# LED_Board_control.net
KiCad netlist of a schematic drawn in Altium Designer
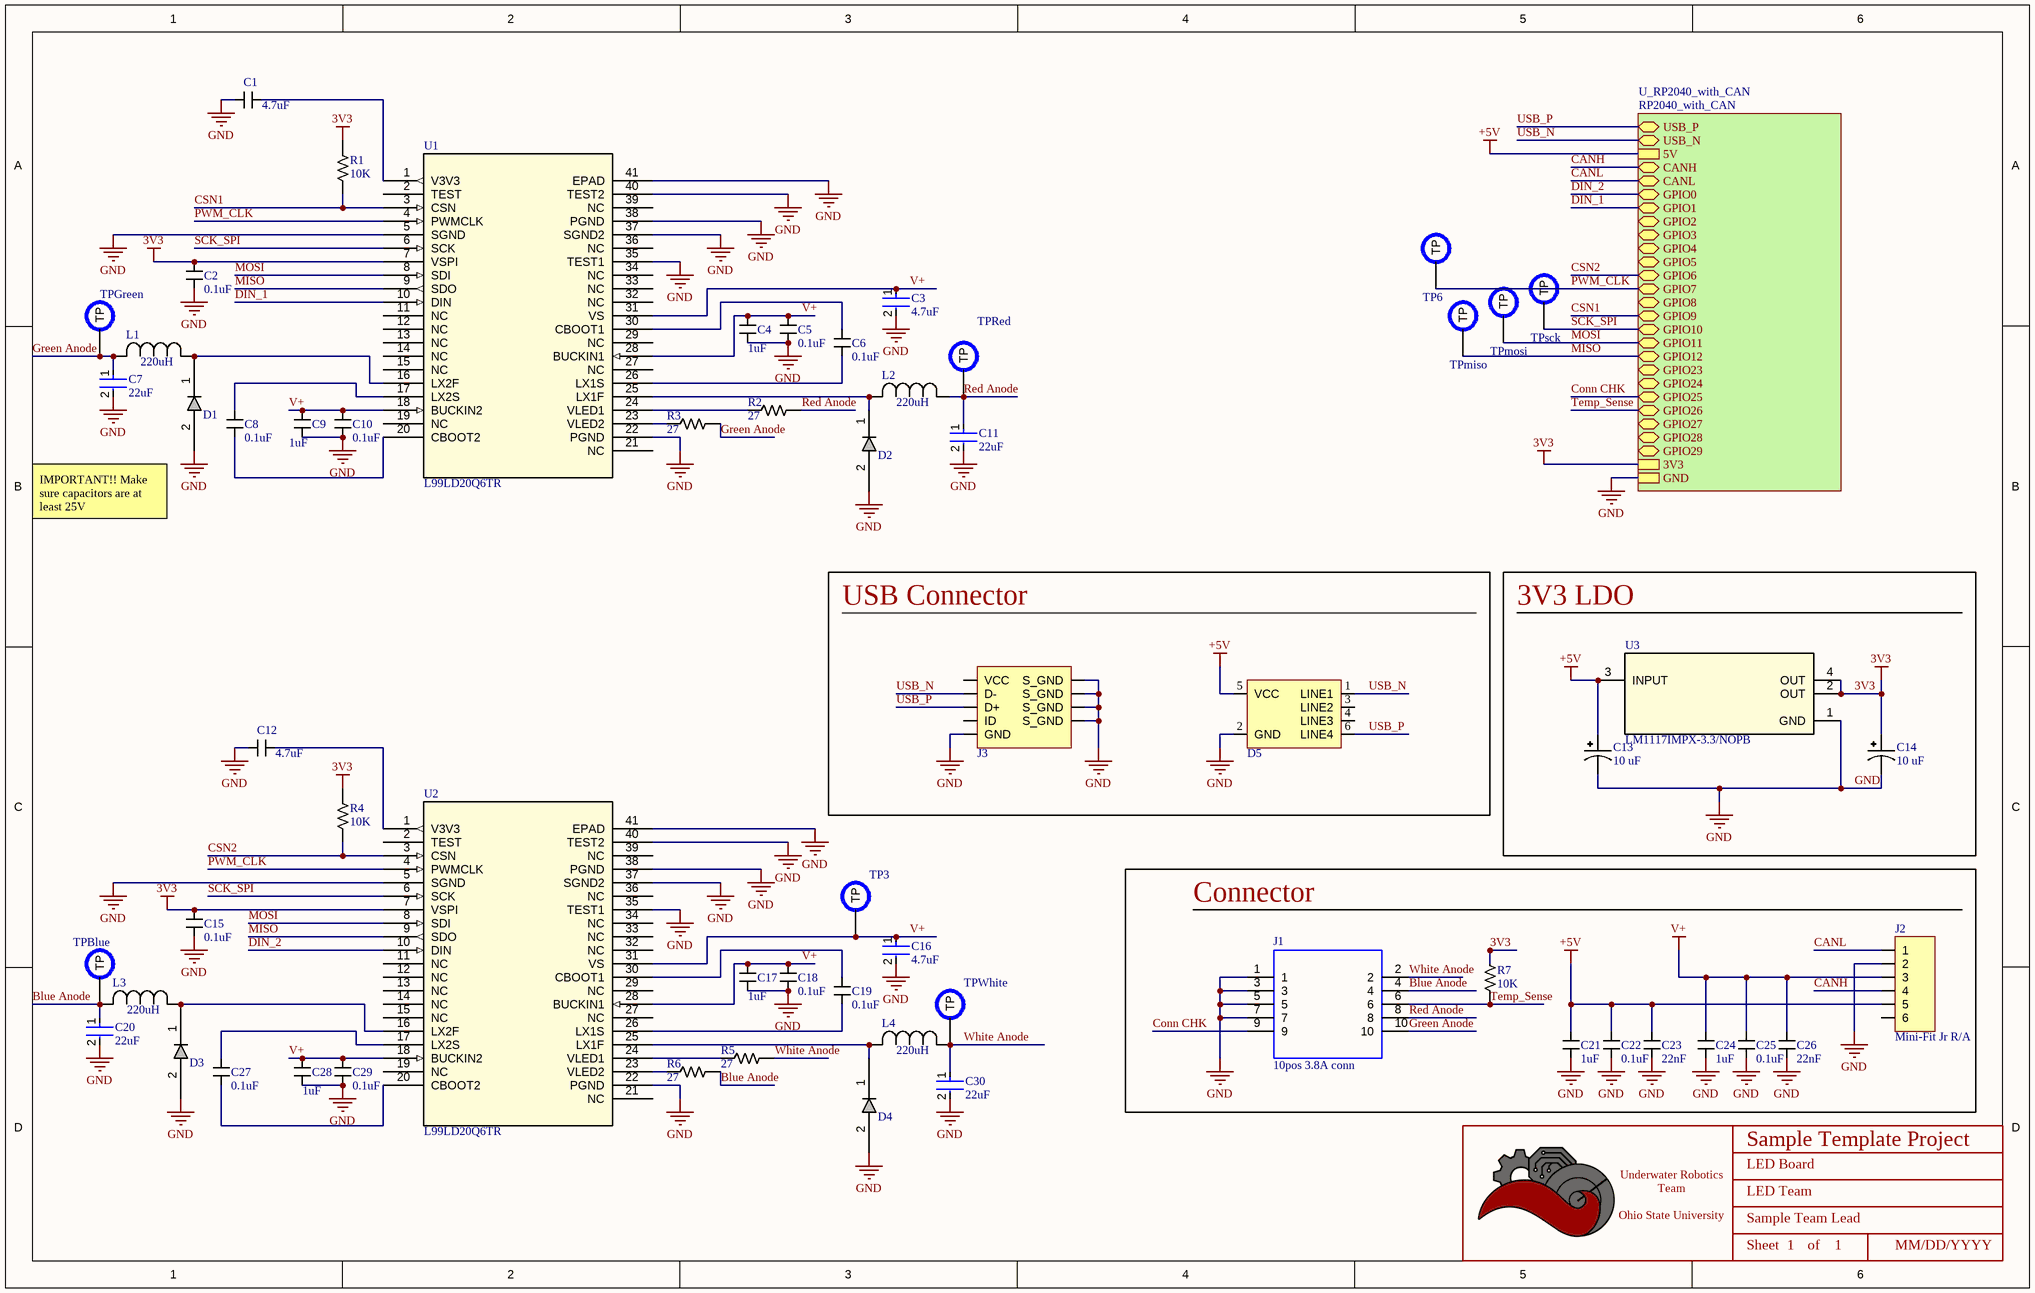
[diagram p0: LED_Board_control.SchDoc]

(export (version "E")
  (design (tool "Eeschema 10.0.6"))
  (components
    (comp (ref "*")
      (value "Title_Block")
      (footprint "LOGO")
      (description "UWRT Schematic Title Block Template\r\n\r\nCreated June 2021, Dylan Trainor")
      (libsource (lib "UWRT") (part "Title_Block"))
    )
    (comp (ref "C1")
      (value "4.7uF")
      (footprint "CAPACITOR_0603")
      (description "Cap 4.7uF 6.3V +/-10%\r\nCeramic 0603")
      (fields
        (field (name "TOLERANCE") "+/- 10%")
        (field (name "VOLTAGE") "6.3V")
        (field (name "MADE BY") "Robert Pafford")
      )
      (libsource (lib "Capacitors") (part "CAPACITOR_4.7uF_0603"))
    )
    (comp (ref "C2")
      (value "0.1uF")
      (footprint "CAPACITOR_0603")
      (description "Cap 100nF 6.3V +/-10%\r\nCeramic 0603")
      (fields
        (field (name "TOLERANCE") "+/- 10%")
        (field (name "VOLTAGE") "6.3V")
        (field (name "MADE BY") "Flip B")
      )
      (libsource (lib "Capacitors") (part "CAPACITOR_0.1uF_0603_1"))
    )
    (comp (ref "C3")
      (value "4.7uF")
      (footprint "CAPACITOR_0603")
      (description "Chip Multilayer Ceramic Capacitors for General Purpose, 0603, 4.7uF, X5R, 15%, 20%, 35V")
      (fields (field (name "TOLERANCE") "20%"))
      (libsource (lib "Capacitors") (part "CAP CERM 4.7UF 20% 35V"))
    )
    (comp (ref "C4")
      (value "1uF")
      (footprint "CAPACITOR_0603")
      (description "Cap 1uF 25V +/-10%\r\nCeramic 0603")
      (fields
        (field (name "TOLERANCE") "+/- 10%")
        (field (name "VOLTAGE") "16V")
        (field (name "MADE BY") "Flip B")
      )
      (libsource (lib "Capacitors") (part "CAPACITOR_1uF_0603_25V"))
    )
    (comp (ref "C5")
      (value "0.1uF")
      (footprint "CAPACITOR_0603")
      (description "Cap 100nF 25V +/-10%\r\nCeramic 0603")
      (fields
        (field (name "TOLERANCE") "+/- 10%")
        (field (name "VOLTAGE") "6.3V")
        (field (name "MADE BY") "Flip B")
      )
      (libsource (lib "Capacitors") (part "CAPACITOR_0.1uF_0603_25V"))
    )
    (comp (ref "C6")
      (value "0.1uF")
      (footprint "CAPACITOR_0603")
      (description "Cap 100nF 25V +/-10%\r\nCeramic 0603")
      (fields
        (field (name "TOLERANCE") "+/- 10%")
        (field (name "VOLTAGE") "6.3V")
        (field (name "MADE BY") "Flip B")
      )
      (libsource (lib "Capacitors") (part "CAPACITOR_0.1uF_0603_25V"))
    )
    (comp (ref "C7")
      (value "22uF")
      (footprint "FP-C2012-125-0_2-MFG")
      (description "Multilayer Ceramic Capacitors 22μF ±20% 35V X5R SMD 0805")
      (fields (field (name "TOLERANCE") "20%"))
      (libsource (lib "Altium Content Vault") (part "b4654b650e69147ec39a6b967a45e02"))
    )
    (comp (ref "C8")
      (value "0.1uF")
      (footprint "CAPACITOR_0603")
      (description "Cap 100nF 25V +/-10%\r\nCeramic 0603")
      (fields
        (field (name "TOLERANCE") "+/- 10%")
        (field (name "VOLTAGE") "6.3V")
        (field (name "MADE BY") "Flip B")
      )
      (libsource (lib "Capacitors") (part "CAPACITOR_0.1uF_0603_25V"))
    )
    (comp (ref "C9")
      (value "1uF")
      (footprint "CAPACITOR_0603")
      (description "Cap 1uF 25V +/-10%\r\nCeramic 0603")
      (fields
        (field (name "TOLERANCE") "+/- 10%")
        (field (name "VOLTAGE") "16V")
        (field (name "MADE BY") "Flip B")
      )
      (libsource (lib "Capacitors") (part "CAPACITOR_1uF_0603_25V"))
    )
    (comp (ref "C10")
      (value "0.1uF")
      (footprint "CAPACITOR_0603")
      (description "Cap 100nF 25V +/-10%\r\nCeramic 0603")
      (fields
        (field (name "TOLERANCE") "+/- 10%")
        (field (name "VOLTAGE") "6.3V")
        (field (name "MADE BY") "Flip B")
      )
      (libsource (lib "Capacitors") (part "CAPACITOR_0.1uF_0603_25V"))
    )
    (comp (ref "C11")
      (value "22uF")
      (footprint "FP-C2012-125-0_2-MFG")
      (description "Multilayer Ceramic Capacitors 22μF ±20% 35V X5R SMD 0805")
      (fields (field (name "TOLERANCE") "20%"))
      (libsource (lib "Altium Content Vault") (part "b4654b650e69147ec39a6b967a45e02"))
    )
    (comp (ref "C12")
      (value "4.7uF")
      (footprint "CAPACITOR_0603")
      (description "Cap 4.7uF 6.3V +/-10%\r\nCeramic 0603")
      (fields
        (field (name "TOLERANCE") "+/- 10%")
        (field (name "VOLTAGE") "6.3V")
        (field (name "MADE BY") "Robert Pafford")
      )
      (libsource (lib "Capacitors") (part "CAPACITOR_4.7uF_0603"))
    )
    (comp (ref "C13")
      (value "10uF Tantalum 16V")
      (footprint "CAPACITOR_1206 - POLAR")
      (description "Cap 10uF 16V +/-20%\r\nTantalum 1206")
      (fields
        (field (name "TOLERANCE") "+/- 10%")
        (field (name "VOLTAGE") "16V")
        (field (name "VALUE (UF)") "10 uF")
        (field (name "MADE BY") "Dylan T")
      )
      (libsource (lib "Capacitors") (part "CAPACITOR_10uF_1206_Tantalum_1"))
    )
    (comp (ref "C14")
      (value "10uF Tantalum 16V")
      (footprint "CAPACITOR_1206 - POLAR")
      (description "Cap 10uF 16V +/-20%\r\nTantalum 1206")
      (fields
        (field (name "TOLERANCE") "+/- 10%")
        (field (name "VOLTAGE") "16V")
        (field (name "VALUE (UF)") "10 uF")
        (field (name "MADE BY") "Dylan T")
      )
      (libsource (lib "Capacitors") (part "CAPACITOR_10uF_1206_Tantalum_1"))
    )
    (comp (ref "C15")
      (value "0.1uF")
      (footprint "CAPACITOR_0603")
      (description "Cap 100nF 6.3V +/-10%\r\nCeramic 0603")
      (fields
        (field (name "TOLERANCE") "+/- 10%")
        (field (name "VOLTAGE") "6.3V")
        (field (name "MADE BY") "Flip B")
      )
      (libsource (lib "Capacitors") (part "CAPACITOR_0.1uF_0603_1"))
    )
    (comp (ref "C16")
      (value "4.7uF")
      (footprint "CAPACITOR_0603")
      (description "Chip Multilayer Ceramic Capacitors for General Purpose, 0603, 4.7uF, X5R, 15%, 20%, 35V")
      (fields (field (name "TOLERANCE") "20%"))
      (libsource (lib "Capacitors") (part "CAP CERM 4.7UF 20% 35V"))
    )
    (comp (ref "C17")
      (value "1uF")
      (footprint "CAPACITOR_0603")
      (description "Cap 1uF 25V +/-10%\r\nCeramic 0603")
      (fields
        (field (name "TOLERANCE") "+/- 10%")
        (field (name "VOLTAGE") "16V")
        (field (name "MADE BY") "Flip B")
      )
      (libsource (lib "Capacitors") (part "CAPACITOR_1uF_0603_25V"))
    )
    (comp (ref "C18")
      (value "0.1uF")
      (footprint "CAPACITOR_0603")
      (description "Cap 100nF 25V +/-10%\r\nCeramic 0603")
      (fields
        (field (name "TOLERANCE") "+/- 10%")
        (field (name "VOLTAGE") "6.3V")
        (field (name "MADE BY") "Flip B")
      )
      (libsource (lib "Capacitors") (part "CAPACITOR_0.1uF_0603_25V"))
    )
    (comp (ref "C19")
      (value "0.1uF")
      (footprint "CAPACITOR_0603")
      (description "Cap 100nF 25V +/-10%\r\nCeramic 0603")
      (fields
        (field (name "TOLERANCE") "+/- 10%")
        (field (name "VOLTAGE") "6.3V")
        (field (name "MADE BY") "Flip B")
      )
      (libsource (lib "Capacitors") (part "CAPACITOR_0.1uF_0603_25V"))
    )
    (comp (ref "C20")
      (value "22uF")
      (footprint "FP-C2012-125-0_2-MFG")
      (description "Multilayer Ceramic Capacitors 22μF ±20% 35V X5R SMD 0805")
      (fields (field (name "TOLERANCE") "20%"))
      (libsource (lib "Altium Content Vault") (part "b4654b650e69147ec39a6b967a45e02"))
    )
    (comp (ref "C21")
      (value "1uF")
      (footprint "CAPACITOR_0603")
      (description "Cap 1uF 16V +/-10%\r\nCeramic 0603")
      (fields
        (field (name "TOLERANCE") "+/- 10%")
        (field (name "VOLTAGE") "16V")
        (field (name "MADE BY") "Flip B")
      )
      (libsource (lib "Capacitors") (part "CAPACITOR_1uF_0603"))
    )
    (comp (ref "C22")
      (value "0.1uF")
      (footprint "CAPACITOR_0805")
      (description "Cap 100nF 50V +/-10%\r\nCeramic 0805")
      (fields
        (field (name "TOLERANCE") "+/- 10%")
        (field (name "VOLTAGE") "50V")
        (field (name "MADE BY") "Robert Pafford")
      )
      (libsource (lib "Capacitors") (part "CAPACITOR_0.1uF_0805"))
    )
    (comp (ref "C23")
      (value "22nF")
      (footprint "CAPACITOR_0402")
      (description "Cap 22nF 25V +/-10%\r\nCeramic 0402")
      (fields
        (field (name "TOLERANCE") "+/- 10%")
        (field (name "VOLTAGE") "25V")
        (field (name "MADE BY") "Robert Pafford")
      )
      (libsource (lib "Capacitors") (part "CAPACITOR_0.022uF_0402"))
    )
    (comp (ref "C24")
      (value "1uF")
      (footprint "CAPACITOR_0603")
      (description "Cap 1uF 16V +/-10%\r\nCeramic 0603")
      (fields
        (field (name "TOLERANCE") "+/- 10%")
        (field (name "VOLTAGE") "16V")
        (field (name "MADE BY") "Flip B")
      )
      (libsource (lib "Capacitors") (part "CAPACITOR_1uF_0603"))
    )
    (comp (ref "C25")
      (value "0.1uF")
      (footprint "CAPACITOR_0805")
      (description "Cap 100nF 50V +/-10%\r\nCeramic 0805")
      (fields
        (field (name "TOLERANCE") "+/- 10%")
        (field (name "VOLTAGE") "50V")
        (field (name "MADE BY") "Robert Pafford")
      )
      (libsource (lib "Capacitors") (part "CAPACITOR_0.1uF_0805"))
    )
    (comp (ref "C26")
      (value "22nF")
      (footprint "CAPACITOR_0402")
      (description "Cap 22nF 25V +/-10%\r\nCeramic 0402")
      (fields
        (field (name "TOLERANCE") "+/- 10%")
        (field (name "VOLTAGE") "25V")
        (field (name "MADE BY") "Robert Pafford")
      )
      (libsource (lib "Capacitors") (part "CAPACITOR_0.022uF_0402"))
    )
    (comp (ref "C27")
      (value "0.1uF")
      (footprint "CAPACITOR_0603")
      (description "Cap 100nF 25V +/-10%\r\nCeramic 0603")
      (fields
        (field (name "TOLERANCE") "+/- 10%")
        (field (name "VOLTAGE") "6.3V")
        (field (name "MADE BY") "Flip B")
      )
      (libsource (lib "Capacitors") (part "CAPACITOR_0.1uF_0603_25V"))
    )
    (comp (ref "C28")
      (value "1uF")
      (footprint "CAPACITOR_0603")
      (description "Cap 1uF 25V +/-10%\r\nCeramic 0603")
      (fields
        (field (name "TOLERANCE") "+/- 10%")
        (field (name "VOLTAGE") "16V")
        (field (name "MADE BY") "Flip B")
      )
      (libsource (lib "Capacitors") (part "CAPACITOR_1uF_0603_25V"))
    )
    (comp (ref "C29")
      (value "0.1uF")
      (footprint "CAPACITOR_0603")
      (description "Cap 100nF 25V +/-10%\r\nCeramic 0603")
      (fields
        (field (name "TOLERANCE") "+/- 10%")
        (field (name "VOLTAGE") "6.3V")
        (field (name "MADE BY") "Flip B")
      )
      (libsource (lib "Capacitors") (part "CAPACITOR_0.1uF_0603_25V"))
    )
    (comp (ref "C30")
      (value "22uF")
      (footprint "FP-C2012-125-0_2-MFG")
      (description "Multilayer Ceramic Capacitors 22μF ±20% 35V X5R SMD 0805")
      (fields (field (name "TOLERANCE") "20%"))
      (libsource (lib "Altium Content Vault") (part "b4654b650e69147ec39a6b967a45e02"))
    )
    (comp (ref "D1")
      (value "CCS15S40,L3F")
      (footprint "SOD-963   CST2C_TOS")
      (description "DIODE SCHOTTKY 40V 1.5A CST2C")
      (fields (field (name "COPYRIGHT") "Copyright (C) 2023 Ultra Librarian. All rights reserved."))
      (libsource (lib "Diodes") (part "SCHOTTKY_40V_1.5A"))
    )
    (comp (ref "D2")
      (value "CCS15S40,L3F")
      (footprint "SOD-963   CST2C_TOS")
      (description "DIODE SCHOTTKY 40V 1.5A CST2C")
      (fields (field (name "COPYRIGHT") "Copyright (C) 2023 Ultra Librarian. All rights reserved."))
      (libsource (lib "Diodes") (part "SCHOTTKY_40V_1.5A"))
    )
    (comp (ref "D3")
      (value "CCS15S40,L3F")
      (footprint "SOD-963   CST2C_TOS")
      (description "DIODE SCHOTTKY 40V 1.5A CST2C")
      (fields (field (name "COPYRIGHT") "Copyright (C) 2023 Ultra Librarian. All rights reserved."))
      (libsource (lib "Diodes") (part "SCHOTTKY_40V_1.5A"))
    )
    (comp (ref "D4")
      (value "CCS15S40,L3F")
      (footprint "SOD-963   CST2C_TOS")
      (description "DIODE SCHOTTKY 40V 1.5A CST2C")
      (fields (field (name "COPYRIGHT") "Copyright (C) 2023 Ultra Librarian. All rights reserved."))
      (libsource (lib "Diodes") (part "SCHOTTKY_40V_1.5A"))
    )
    (comp (ref "D5")
      (value "TVS DIODE 5VWM 25VC SOT23-6")
      (footprint "SOT 23-6L")
      (description "25V Clamp 6A (8/20µs) Ipp Tvs Diode Surface Mount SOT-23-6")
      (fields (field (name "MADE BY") "Robert Pafford"))
      (libsource (lib "Diodes") (part "RCLAMP0504S.TCT"))
    )
    (comp (ref "J1")
      (value "10pos 3.8A conn")
      (footprint "Connectors:SAMTEC-LS2-105-01-X-D-RA1")
      (description "10 Position Connector Self Mating, Non-Gendered, Hermaphroditic Through Hole, Right Angle Gold")
      (fields (field (name "MP") "SAMTEC-LS2-105-01-X-D-RA1"))
      (libsource (lib "Connectors") (part "SAMTEC-LS2-105-01-X-D-RA1"))
    )
    (comp (ref "J2")
      (value "Mini-Fit Jr R/A")
      (footprint "CONN_MOLEX_MINIFIT JR_6 POS_R/A")
      (description "Molex Minifit Jr. 5569 \r\n6 Pos R/A Natural")
      (fields (field (name "MANUFACTURER") "Molex") (field (name "CREATED BY") "Flip B"))
      (libsource (lib "Connectors") (part "CONN_MOLEX_MINIFIT JR_6POS_R/A"))
    )
    (comp (ref "J3")
      (value "USB_MICRO R/A")
      (footprint "CONN_MINIUSB")
      (description "Amphenol Micro USB-B\r\nUSB2.0 5 Pin Right Angle SMD")
      (fields (field (name "MANUFACTURER") "Amphenol") (field (name "CREATED BY") "Flip B"))
      (libsource (lib "Connectors") (part "CONN_MICROUSB"))
    )
    (comp (ref "L1")
      (value "SRR1280-221K")
      (footprint "IND_BOURNS_SRR1280")
      (description "220 µH Shielded Drum Core, Wirewound Inductor 1.6 A 400mOhm Max Nonstandard")
      (fields (field (name "COPYRIGHT") "Copyright (C) 2023 Ultra Librarian. All rights reserved."))
      (libsource (lib "Inductors") (part "INDUCTOR_SRR1280-221K"))
    )
    (comp (ref "L2")
      (value "SRR1280-221K")
      (footprint "IND_BOURNS_SRR1280")
      (description "220 µH Shielded Drum Core, Wirewound Inductor 1.6 A 400mOhm Max Nonstandard")
      (fields (field (name "COPYRIGHT") "Copyright (C) 2023 Ultra Librarian. All rights reserved."))
      (libsource (lib "Inductors") (part "INDUCTOR_SRR1280-221K"))
    )
    (comp (ref "L3")
      (value "SRR1280-221K")
      (footprint "IND_BOURNS_SRR1280")
      (description "220 µH Shielded Drum Core, Wirewound Inductor 1.6 A 400mOhm Max Nonstandard")
      (fields (field (name "COPYRIGHT") "Copyright (C) 2023 Ultra Librarian. All rights reserved."))
      (libsource (lib "Inductors") (part "INDUCTOR_SRR1280-221K"))
    )
    (comp (ref "L4")
      (value "SRR1280-221K")
      (footprint "IND_BOURNS_SRR1280")
      (description "220 µH Shielded Drum Core, Wirewound Inductor 1.6 A 400mOhm Max Nonstandard")
      (fields (field (name "COPYRIGHT") "Copyright (C) 2023 Ultra Librarian. All rights reserved."))
      (libsource (lib "Inductors") (part "INDUCTOR_SRR1280-221K"))
    )
    (comp (ref "R1")
      (value "10k Ohm 1% 1/16W")
      (footprint "RESISTOR_0402")
      (description "RES 10k OHM 1% 1/16W 0402")
      (fields
        (field (name "TOLERANCE") "+/- 1%")
        (field (name "VALUE  (OHMS)") "10K")
        (field (name "MADE BY") "Robert Pafford")
      )
      (libsource (lib "Resistors") (part "RESISTOR_10K_0402"))
    )
    (comp (ref "R2")
      (value "27 Ohm 5% 1/8W")
      (footprint "RESISTOR_0603")
      (description "RES 27 OHM 5% 1/8W 0603")
      (fields
        (field (name "TOLERANCE") "+/- 5%")
        (field (name "VALUE  (OHMS)") "27")
        (field (name "MADE BY") "Robert Pafford")
      )
      (libsource (lib "Resistors") (part "RESISTOR_27_0603"))
    )
    (comp (ref "R3")
      (value "27 Ohm 5% 1/8W")
      (footprint "RESISTOR_0603")
      (description "RES 27 OHM 5% 1/8W 0603")
      (fields
        (field (name "TOLERANCE") "+/- 5%")
        (field (name "VALUE  (OHMS)") "27")
        (field (name "MADE BY") "Robert Pafford")
      )
      (libsource (lib "Resistors") (part "RESISTOR_27_0603"))
    )
    (comp (ref "R4")
      (value "10k Ohm 1% 1/16W")
      (footprint "RESISTOR_0402")
      (description "RES 10k OHM 1% 1/16W 0402")
      (fields
        (field (name "TOLERANCE") "+/- 1%")
        (field (name "VALUE  (OHMS)") "10K")
        (field (name "MADE BY") "Robert Pafford")
      )
      (libsource (lib "Resistors") (part "RESISTOR_10K_0402"))
    )
    (comp (ref "R5")
      (value "27 Ohm 5% 1/8W")
      (footprint "RESISTOR_0603")
      (description "RES 27 OHM 5% 1/8W 0603")
      (fields
        (field (name "TOLERANCE") "+/- 5%")
        (field (name "VALUE  (OHMS)") "27")
        (field (name "MADE BY") "Robert Pafford")
      )
      (libsource (lib "Resistors") (part "RESISTOR_27_0603"))
    )
    (comp (ref "R6")
      (value "27 Ohm 5% 1/8W")
      (footprint "RESISTOR_0603")
      (description "RES 27 OHM 5% 1/8W 0603")
      (fields
        (field (name "TOLERANCE") "+/- 5%")
        (field (name "VALUE  (OHMS)") "27")
        (field (name "MADE BY") "Robert Pafford")
      )
      (libsource (lib "Resistors") (part "RESISTOR_27_0603"))
    )
    (comp (ref "R7")
      (value "10k Ohm 0.5% 1/10W")
      (footprint "RESISTOR_0603")
      (description "RES 10k OHM 0.5% 1/10W 0603")
      (fields
        (field (name "TOLERANCE") "+/- 0.5%")
        (field (name "VALUE  (OHMS)") "10K")
        (field (name "MADE BY") "Robert Pafford")
      )
      (libsource (lib "Resistors") (part "RESISTOR_10K_0.5%_0603"))
    )
    (comp (ref "TP3")
      (value "PCB Test Point")
      (footprint "TESTPOINT_1.2MM")
      (fields (field (name "MADE BY") "Robert Pafford"))
      (libsource (lib "Connectors") (part "TESTPOINT"))
    )
    (comp (ref "TP6")
      (value "PCB Test Point")
      (footprint "TESTPOINT_1.2MM")
      (fields (field (name "MADE BY") "Robert Pafford"))
      (libsource (lib "Connectors") (part "TESTPOINT"))
    )
    (comp (ref "TPBlue")
      (value "PCB Test Point")
      (footprint "TESTPOINT_1.2MM")
      (fields (field (name "MADE BY") "Robert Pafford"))
      (libsource (lib "Connectors") (part "TESTPOINT"))
    )
    (comp (ref "TPGreen")
      (value "PCB Test Point")
      (footprint "TESTPOINT_1.2MM")
      (fields (field (name "MADE BY") "Robert Pafford"))
      (libsource (lib "Connectors") (part "TESTPOINT"))
    )
    (comp (ref "TPmiso")
      (value "PCB Test Point")
      (footprint "TESTPOINT_1.2MM")
      (fields (field (name "MADE BY") "Robert Pafford"))
      (libsource (lib "Connectors") (part "TESTPOINT"))
    )
    (comp (ref "TPmosi")
      (value "PCB Test Point")
      (footprint "TESTPOINT_1.2MM")
      (fields (field (name "MADE BY") "Robert Pafford"))
      (libsource (lib "Connectors") (part "TESTPOINT"))
    )
    (comp (ref "TPRed")
      (value "PCB Test Point")
      (footprint "TESTPOINT_1.2MM")
      (fields (field (name "MADE BY") "Robert Pafford"))
      (libsource (lib "Connectors") (part "TESTPOINT"))
    )
    (comp (ref "TPsck")
      (value "PCB Test Point")
      (footprint "TESTPOINT_1.2MM")
      (fields (field (name "MADE BY") "Robert Pafford"))
      (libsource (lib "Connectors") (part "TESTPOINT"))
    )
    (comp (ref "TPWhite")
      (value "PCB Test Point")
      (footprint "TESTPOINT_1.2MM")
      (fields (field (name "MADE BY") "Robert Pafford"))
      (libsource (lib "Connectors") (part "TESTPOINT"))
    )
    (comp (ref "U1")
      (value "L99LD20Q6TR")
      (footprint "L99LD20Q6TR")
      (description "IC LED DRVR RGLTR PWM 1.5A 40QFN")
      (fields (field (name "COPYRIGHT") "Copyright (C) 2023 Ultra Librarian. All rights reserved."))
      (libsource (lib "Integrated Circuits") (part "L99LD20Q6TR"))
    )
    (comp (ref "U2")
      (value "L99LD20Q6TR")
      (footprint "L99LD20Q6TR")
      (description "IC LED DRVR RGLTR PWM 1.5A 40QFN")
      (fields (field (name "COPYRIGHT") "Copyright (C) 2023 Ultra Librarian. All rights reserved."))
      (libsource (lib "Integrated Circuits") (part "L99LD20Q6TR"))
    )
    (comp (ref "U3")
      (value "LM1117IMPX-3.3/NOPB")
      (footprint "SOT-223-4")
      (description "IC REG LIN 3.3V 800MA SOT223-4")
      (fields
        (field (name "PARTNUMBER") "LM1117IMP-3.3/NOPB")
        (field (name "MANUFACTURER") "Texas Instruments")
        (field (name "CREATED BY") "Dylan T")
      )
      (libsource (lib "Converter") (part "LM1117IMPX-3.3/NOPB"))
    )
  )
  (nets
    (net (code "1") (name "+5V") (class "Default")
      (node (ref "C13") (pin "1") (pintype "passive"))
      (node (ref "C21") (pin "1") (pinfunction "1_1") (pintype "passive"))
      (node (ref "C22") (pin "1") (pinfunction "1_1") (pintype "passive"))
      (node (ref "C23") (pin "1") (pinfunction "1_1") (pintype "passive"))
      (node (ref "D5") (pin "5") (pinfunction "VCC_5") (pintype "power_in"))
      (node (ref "J2") (pin "5") (pinfunction "5_5") (pintype "passive"))
      (node (ref "U3") (pin "3") (pinfunction "INPUT_3") (pintype "power_in"))
    )
    (net (code "2") (name "/Blue Anode") (class "Default")
      (node (ref "C20") (pin "1") (pinfunction "1_1") (pintype "passive"))
      (node (ref "J1") (pin "4") (pinfunction "4_4") (pintype "passive"))
      (node (ref "L3") (pin "2") (pinfunction "2_2") (pintype "passive"))
      (node (ref "R6") (pin "1") (pinfunction "1_1") (pintype "passive"))
      (node (ref "TPBlue") (pin "TP") (pinfunction "TP_TP") (pintype "passive"))
    )
    (net (code "3") (name "/CANH") (class "Default")
      (node (ref "J2") (pin "4") (pinfunction "4_4") (pintype "passive"))
    )
    (net (code "4") (name "/CANL") (class "Default")
      (node (ref "J2") (pin "1") (pinfunction "1_1") (pintype "passive"))
    )
    (net (code "5") (name "/CSN1") (class "Default")
      (node (ref "R1") (pin "2") (pinfunction "2_2") (pintype "passive"))
      (node (ref "U1") (pin "3") (pinfunction "CSN_3") (pintype "input"))
    )
    (net (code "6") (name "/CSN2") (class "Default")
      (node (ref "R4") (pin "2") (pinfunction "2_2") (pintype "passive"))
      (node (ref "U2") (pin "3") (pinfunction "CSN_3") (pintype "input"))
    )
    (net (code "7") (name "/Conn CHK") (class "Default")
      (node (ref "J1") (pin "9") (pinfunction "9_9") (pintype "passive"))
    )
    (net (code "8") (name "/DIN_1") (class "Default")
      (node (ref "U1") (pin "10") (pinfunction "DIN_10") (pintype "input"))
    )
    (net (code "9") (name "/DIN_2") (class "Default")
      (node (ref "U2") (pin "10") (pinfunction "DIN_10") (pintype "input"))
    )
    (net (code "20") (name "/Green Anode") (class "Default")
      (node (ref "C7") (pin "1") (pinfunction "1_1") (pintype "passive"))
      (node (ref "J1") (pin "10") (pinfunction "10_10") (pintype "passive"))
      (node (ref "L1") (pin "2") (pinfunction "2_2") (pintype "passive"))
      (node (ref "R3") (pin "1") (pinfunction "1_1") (pintype "passive"))
      (node (ref "TPGreen") (pin "TP") (pinfunction "TP_TP") (pintype "passive"))
    )
    (net (code "21") (name "/MISO") (class "Default")
      (node (ref "TPmiso") (pin "TP") (pinfunction "TP_TP") (pintype "passive"))
      (node (ref "U1") (pin "9") (pinfunction "SDO_9") (pintype "output"))
      (node (ref "U2") (pin "9") (pinfunction "SDO_9") (pintype "output"))
    )
    (net (code "22") (name "/MOSI") (class "Default")
      (node (ref "TPmosi") (pin "TP") (pinfunction "TP_TP") (pintype "passive"))
      (node (ref "U1") (pin "8") (pinfunction "SDI_8") (pintype "input"))
      (node (ref "U2") (pin "8") (pinfunction "SDI_8") (pintype "input"))
    )
    (net (code "23") (name "/PWM_CLK") (class "Default")
      (node (ref "TP6") (pin "TP") (pinfunction "TP_TP") (pintype "passive"))
      (node (ref "U1") (pin "4") (pinfunction "PWMCLK_4") (pintype "input"))
      (node (ref "U2") (pin "4") (pinfunction "PWMCLK_4") (pintype "input"))
    )
    (net (code "24") (name "/Red Anode") (class "Default")
      (node (ref "C11") (pin "1") (pinfunction "1_1") (pintype "passive"))
      (node (ref "J1") (pin "8") (pinfunction "8_8") (pintype "passive"))
      (node (ref "L2") (pin "1") (pinfunction "1_1") (pintype "passive"))
      (node (ref "R2") (pin "1") (pinfunction "1_1") (pintype "passive"))
      (node (ref "TPRed") (pin "TP") (pinfunction "TP_TP") (pintype "passive"))
    )
    (net (code "25") (name "/SCK_SPI") (class "Default")
      (node (ref "TPsck") (pin "TP") (pinfunction "TP_TP") (pintype "passive"))
      (node (ref "U1") (pin "6") (pinfunction "SCK_6") (pintype "input"))
      (node (ref "U2") (pin "6") (pinfunction "SCK_6") (pintype "input"))
    )
    (net (code "26") (name "/Temp_Sense") (class "Default")
      (node (ref "J1") (pin "6") (pinfunction "6_6") (pintype "passive"))
      (node (ref "R7") (pin "2") (pinfunction "2_2") (pintype "passive"))
    )
    (net (code "27") (name "/USB_N") (class "Default")
      (node (ref "D5") (pin "1") (pinfunction "LINE1_1") (pintype "passive"))
      (node (ref "J3") (pin "2") (pinfunction "D-_2") (pintype "passive"))
    )
    (net (code "28") (name "/USB_P") (class "Default")
      (node (ref "D5") (pin "6") (pinfunction "LINE4_6") (pintype "passive"))
      (node (ref "J3") (pin "3") (pinfunction "D+_3") (pintype "passive"))
    )
    (net (code "29") (name "/White Anode") (class "Default")
      (node (ref "C30") (pin "1") (pinfunction "1_1") (pintype "passive"))
      (node (ref "J1") (pin "2") (pinfunction "2_2") (pintype "passive"))
      (node (ref "L4") (pin "1") (pinfunction "1_1") (pintype "passive"))
      (node (ref "R5") (pin "1") (pinfunction "1_1") (pintype "passive"))
      (node (ref "TPWhite") (pin "TP") (pinfunction "TP_TP") (pintype "passive"))
    )
    (net (code "30") (name "3V3") (class "Default")
      (node (ref "C14") (pin "1") (pintype "passive"))
      (node (ref "C15") (pin "1") (pinfunction "1_1") (pintype "passive"))
      (node (ref "C2") (pin "1") (pinfunction "1_1") (pintype "passive"))
      (node (ref "R1") (pin "1") (pinfunction "1_1") (pintype "passive"))
      (node (ref "R4") (pin "1") (pinfunction "1_1") (pintype "passive"))
      (node (ref "R7") (pin "1") (pinfunction "1_1") (pintype "passive"))
      (node (ref "U1") (pin "7") (pinfunction "VSPI_7") (pintype "passive"))
      (node (ref "U2") (pin "7") (pinfunction "VSPI_7") (pintype "passive"))
      (node (ref "U3") (pin "2") (pinfunction "OUT_2") (pintype "power_in"))
      (node (ref "U3") (pin "4") (pinfunction "OUT_4") (pintype "power_in"))
    )
    (net (code "31") (name "GND") (class "Default")
      (node (ref "C1") (pin "2") (pinfunction "2_2") (pintype "passive"))
      (node (ref "C10") (pin "2") (pinfunction "2_2") (pintype "passive"))
      (node (ref "C11") (pin "2") (pinfunction "2_2") (pintype "passive"))
      (node (ref "C12") (pin "2") (pinfunction "2_2") (pintype "passive"))
      (node (ref "C13") (pin "2") (pintype "passive"))
      (node (ref "C14") (pin "2") (pintype "passive"))
      (node (ref "C15") (pin "2") (pinfunction "2_2") (pintype "passive"))
      (node (ref "C16") (pin "2") (pinfunction "2_2") (pintype "passive"))
      (node (ref "C17") (pin "1") (pinfunction "1_1") (pintype "passive"))
      (node (ref "C18") (pin "2") (pinfunction "2_2") (pintype "passive"))
      (node (ref "C2") (pin "2") (pinfunction "2_2") (pintype "passive"))
      (node (ref "C20") (pin "2") (pinfunction "2_2") (pintype "passive"))
      (node (ref "C21") (pin "2") (pinfunction "2_2") (pintype "passive"))
      (node (ref "C22") (pin "2") (pinfunction "2_2") (pintype "passive"))
      (node (ref "C23") (pin "2") (pinfunction "2_2") (pintype "passive"))
      (node (ref "C24") (pin "2") (pinfunction "2_2") (pintype "passive"))
      (node (ref "C25") (pin "2") (pinfunction "2_2") (pintype "passive"))
      (node (ref "C26") (pin "2") (pinfunction "2_2") (pintype "passive"))
      (node (ref "C28") (pin "1") (pinfunction "1_1") (pintype "passive"))
      (node (ref "C29") (pin "2") (pinfunction "2_2") (pintype "passive"))
      (node (ref "C3") (pin "2") (pinfunction "2_2") (pintype "passive"))
      (node (ref "C30") (pin "2") (pinfunction "2_2") (pintype "passive"))
      (node (ref "C4") (pin "1") (pinfunction "1_1") (pintype "passive"))
      (node (ref "C5") (pin "2") (pinfunction "2_2") (pintype "passive"))
      (node (ref "C7") (pin "2") (pinfunction "2_2") (pintype "passive"))
      (node (ref "C9") (pin "1") (pinfunction "1_1") (pintype "passive"))
      (node (ref "D1") (pin "2") (pinfunction "2_2") (pintype "passive"))
      (node (ref "D2") (pin "2") (pinfunction "2_2") (pintype "passive"))
      (node (ref "D3") (pin "2") (pinfunction "2_2") (pintype "passive"))
      (node (ref "D4") (pin "2") (pinfunction "2_2") (pintype "passive"))
      (node (ref "D5") (pin "2") (pinfunction "GND_2") (pintype "power_in"))
      (node (ref "J1") (pin "1") (pinfunction "1_1") (pintype "passive"))
      (node (ref "J1") (pin "3") (pinfunction "3_3") (pintype "passive"))
      (node (ref "J1") (pin "5") (pinfunction "5_5") (pintype "passive"))
      (node (ref "J1") (pin "7") (pinfunction "7_7") (pintype "passive"))
      (node (ref "J2") (pin "2") (pinfunction "2_2") (pintype "passive"))
      (node (ref "J3") (pin "5") (pinfunction "GND_5") (pintype "passive"))
      (node (ref "J3") (pin "6") (pinfunction "S_GND_6") (pintype "passive"))
      (node (ref "J3") (pin "7") (pinfunction "S_GND_7") (pintype "passive"))
      (node (ref "J3") (pin "8") (pinfunction "S_GND_8") (pintype "passive"))
      (node (ref "J3") (pin "9") (pinfunction "S_GND_9") (pintype "passive"))
      (node (ref "U1") (pin "22") (pinfunction "PGND_22") (pintype "power_in"))
      (node (ref "U1") (pin "35") (pinfunction "TEST1_35") (pintype "passive"))
      (node (ref "U1") (pin "37") (pinfunction "SGND2_37") (pintype "power_in"))
      (node (ref "U1") (pin "38") (pinfunction "PGND_38") (pintype "power_in"))
      (node (ref "U1") (pin "40") (pinfunction "TEST2_40") (pintype "passive"))
      (node (ref "U1") (pin "41") (pinfunction "EPAD_41") (pintype "power_in"))
      (node (ref "U1") (pin "5") (pinfunction "SGND_5") (pintype "power_in"))
      (node (ref "U2") (pin "22") (pinfunction "PGND_22") (pintype "power_in"))
      (node (ref "U2") (pin "35") (pinfunction "TEST1_35") (pintype "passive"))
      (node (ref "U2") (pin "37") (pinfunction "SGND2_37") (pintype "power_in"))
      (node (ref "U2") (pin "38") (pinfunction "PGND_38") (pintype "power_in"))
      (node (ref "U2") (pin "40") (pinfunction "TEST2_40") (pintype "passive"))
      (node (ref "U2") (pin "41") (pinfunction "EPAD_41") (pintype "power_in"))
      (node (ref "U2") (pin "5") (pinfunction "SGND_5") (pintype "power_in"))
      (node (ref "U3") (pin "1") (pinfunction "GND_1") (pintype "power_in"))
    )
    (net (code "32") (name "Net-(U1-CBOOT1)") (class "Default")
      (node (ref "C6") (pin "1") (pinfunction "1_1") (pintype "passive"))
      (node (ref "U1") (pin "30") (pinfunction "CBOOT1_30") (pintype "passive"))
    )
    (net (code "33") (name "Net-(U1-CBOOT2)") (class "Default")
      (node (ref "C8") (pin "2") (pinfunction "2_2") (pintype "passive"))
      (node (ref "U1") (pin "20") (pinfunction "CBOOT2_20") (pintype "passive"))
    )
    (net (code "34") (name "Net-(U1-LX1F)") (class "Default")
      (node (ref "D2") (pin "1") (pinfunction "1_1") (pintype "passive"))
      (node (ref "L2") (pin "2") (pinfunction "2_2") (pintype "passive"))
      (node (ref "U1") (pin "25") (pinfunction "LX1F_25") (pintype "passive"))
    )
    (net (code "35") (name "Net-(U1-LX1S)") (class "Default")
      (node (ref "C6") (pin "2") (pinfunction "2_2") (pintype "passive"))
      (node (ref "U1") (pin "26") (pinfunction "LX1S_26") (pintype "passive"))
    )
    (net (code "36") (name "Net-(U1-LX2F)") (class "Default")
      (node (ref "D1") (pin "1") (pinfunction "1_1") (pintype "passive"))
      (node (ref "L1") (pin "1") (pinfunction "1_1") (pintype "passive"))
      (node (ref "U1") (pin "16") (pinfunction "LX2F_16") (pintype "passive"))
    )
    (net (code "37") (name "Net-(U1-LX2S)") (class "Default")
      (node (ref "C8") (pin "1") (pinfunction "1_1") (pintype "passive"))
      (node (ref "U1") (pin "17") (pinfunction "LX2S_17") (pintype "passive"))
    )
    (net (code "38") (name "Net-(U1-V3V3)") (class "Default")
      (node (ref "C1") (pin "1") (pinfunction "1_1") (pintype "passive"))
      (node (ref "U1") (pin "1") (pinfunction "V3V3_1") (pintype "output"))
    )
    (net (code "39") (name "Net-(U1-VLED1)") (class "Default")
      (node (ref "R2") (pin "2") (pinfunction "2_2") (pintype "passive"))
      (node (ref "U1") (pin "24") (pinfunction "VLED1_24") (pintype "passive"))
    )
    (net (code "40") (name "Net-(U1-VLED2)") (class "Default")
      (node (ref "R3") (pin "2") (pinfunction "2_2") (pintype "passive"))
      (node (ref "U1") (pin "23") (pinfunction "VLED2_23") (pintype "passive"))
    )
    (net (code "41") (name "Net-(U2-CBOOT1)") (class "Default")
      (node (ref "C19") (pin "1") (pinfunction "1_1") (pintype "passive"))
      (node (ref "U2") (pin "30") (pinfunction "CBOOT1_30") (pintype "passive"))
    )
    (net (code "42") (name "Net-(U2-CBOOT2)") (class "Default")
      (node (ref "C27") (pin "2") (pinfunction "2_2") (pintype "passive"))
      (node (ref "U2") (pin "20") (pinfunction "CBOOT2_20") (pintype "passive"))
    )
    (net (code "43") (name "Net-(U2-LX1F)") (class "Default")
      (node (ref "D4") (pin "1") (pinfunction "1_1") (pintype "passive"))
      (node (ref "L4") (pin "2") (pinfunction "2_2") (pintype "passive"))
      (node (ref "U2") (pin "25") (pinfunction "LX1F_25") (pintype "passive"))
    )
    (net (code "44") (name "Net-(U2-LX1S)") (class "Default")
      (node (ref "C19") (pin "2") (pinfunction "2_2") (pintype "passive"))
      (node (ref "U2") (pin "26") (pinfunction "LX1S_26") (pintype "passive"))
    )
    (net (code "45") (name "Net-(U2-LX2F)") (class "Default")
      (node (ref "D3") (pin "1") (pinfunction "1_1") (pintype "passive"))
      (node (ref "L3") (pin "1") (pinfunction "1_1") (pintype "passive"))
      (node (ref "U2") (pin "16") (pinfunction "LX2F_16") (pintype "passive"))
    )
    (net (code "46") (name "Net-(U2-LX2S)") (class "Default")
      (node (ref "C27") (pin "1") (pinfunction "1_1") (pintype "passive"))
      (node (ref "U2") (pin "17") (pinfunction "LX2S_17") (pintype "passive"))
    )
    (net (code "47") (name "Net-(U2-V3V3)") (class "Default")
      (node (ref "C12") (pin "1") (pinfunction "1_1") (pintype "passive"))
      (node (ref "U2") (pin "1") (pinfunction "V3V3_1") (pintype "output"))
    )
    (net (code "48") (name "Net-(U2-VLED1)") (class "Default")
      (node (ref "R5") (pin "2") (pinfunction "2_2") (pintype "passive"))
      (node (ref "U2") (pin "24") (pinfunction "VLED1_24") (pintype "passive"))
    )
    (net (code "49") (name "Net-(U2-VLED2)") (class "Default")
      (node (ref "R6") (pin "2") (pinfunction "2_2") (pintype "passive"))
      (node (ref "U2") (pin "23") (pinfunction "VLED2_23") (pintype "passive"))
    )
    (net (code "50") (name "V+") (class "Default")
      (node (ref "C10") (pin "1") (pinfunction "1_1") (pintype "passive"))
      (node (ref "C16") (pin "1") (pinfunction "1_1") (pintype "passive"))
      (node (ref "C17") (pin "2") (pinfunction "2_2") (pintype "passive"))
      (node (ref "C18") (pin "1") (pinfunction "1_1") (pintype "passive"))
      (node (ref "C24") (pin "1") (pinfunction "1_1") (pintype "passive"))
      (node (ref "C25") (pin "1") (pinfunction "1_1") (pintype "passive"))
      (node (ref "C26") (pin "1") (pinfunction "1_1") (pintype "passive"))
      (node (ref "C28") (pin "2") (pinfunction "2_2") (pintype "passive"))
      (node (ref "C29") (pin "1") (pinfunction "1_1") (pintype "passive"))
      (node (ref "C3") (pin "1") (pinfunction "1_1") (pintype "passive"))
      (node (ref "C4") (pin "2") (pinfunction "2_2") (pintype "passive"))
      (node (ref "C5") (pin "1") (pinfunction "1_1") (pintype "passive"))
      (node (ref "C9") (pin "2") (pinfunction "2_2") (pintype "passive"))
      (node (ref "J2") (pin "3") (pinfunction "3_3") (pintype "passive"))
      (node (ref "TP3") (pin "TP") (pinfunction "TP_TP") (pintype "passive"))
      (node (ref "U1") (pin "18") (pinfunction "BUCKIN2_18") (pintype "input"))
      (node (ref "U1") (pin "28") (pinfunction "BUCKIN1_28") (pintype "input"))
      (node (ref "U1") (pin "31") (pinfunction "VS_31") (pintype "passive"))
      (node (ref "U2") (pin "18") (pinfunction "BUCKIN2_18") (pintype "input"))
      (node (ref "U2") (pin "28") (pinfunction "BUCKIN1_28") (pintype "input"))
      (node (ref "U2") (pin "31") (pinfunction "VS_31") (pintype "passive"))
    )
    (net (code "51") (name "unconnected-(D5-LINE2-Pad3)") (class "Default")
      (node (ref "D5") (pin "3") (pinfunction "LINE2_3") (pintype "passive"))
    )
    (net (code "52") (name "unconnected-(D5-LINE3-Pad4)") (class "Default")
      (node (ref "D5") (pin "4") (pinfunction "LINE3_4") (pintype "passive"))
    )
    (net (code "53") (name "unconnected-(J2-Pad6)") (class "Default")
      (node (ref "J2") (pin "6") (pinfunction "6_6") (pintype "passive"))
    )
    (net (code "54") (name "unconnected-(J3-ID-Pad4)") (class "Default")
      (node (ref "J3") (pin "4") (pinfunction "ID_4") (pintype "passive"))
    )
    (net (code "55") (name "unconnected-(J3-VCC-Pad1)") (class "Default")
      (node (ref "J3") (pin "1") (pinfunction "VCC_1") (pintype "passive"))
    )
    (net (code "56") (name "unconnected-(U1-NC-Pad11)") (class "Default")
      (node (ref "U1") (pin "11") (pinfunction "NC_11") (pintype "passive"))
    )
    (net (code "57") (name "unconnected-(U1-NC-Pad12)") (class "Default")
      (node (ref "U1") (pin "12") (pinfunction "NC_12") (pintype "passive"))
    )
    (net (code "58") (name "unconnected-(U1-NC-Pad13)") (class "Default")
      (node (ref "U1") (pin "13") (pinfunction "NC_13") (pintype "passive"))
    )
    (net (code "59") (name "unconnected-(U1-NC-Pad14)") (class "Default")
      (node (ref "U1") (pin "14") (pinfunction "NC_14") (pintype "passive"))
    )
    (net (code "60") (name "unconnected-(U1-NC-Pad15)") (class "Default")
      (node (ref "U1") (pin "15") (pinfunction "NC_15") (pintype "passive"))
    )
    (net (code "61") (name "unconnected-(U1-NC-Pad19)") (class "Default")
      (node (ref "U1") (pin "19") (pinfunction "NC_19") (pintype "passive"))
    )
    (net (code "62") (name "unconnected-(U1-NC-Pad21)") (class "Default")
      (node (ref "U1") (pin "21") (pinfunction "NC_21") (pintype "passive"))
    )
    (net (code "63") (name "unconnected-(U1-NC-Pad27)") (class "Default")
      (node (ref "U1") (pin "27") (pinfunction "NC_27") (pintype "passive"))
    )
    (net (code "64") (name "unconnected-(U1-NC-Pad29)") (class "Default")
      (node (ref "U1") (pin "29") (pinfunction "NC_29") (pintype "passive"))
    )
    (net (code "65") (name "unconnected-(U1-NC-Pad32)") (class "Default")
      (node (ref "U1") (pin "32") (pinfunction "NC_32") (pintype "passive"))
    )
    (net (code "66") (name "unconnected-(U1-NC-Pad33)") (class "Default")
      (node (ref "U1") (pin "33") (pinfunction "NC_33") (pintype "passive"))
    )
    (net (code "67") (name "unconnected-(U1-NC-Pad34)") (class "Default")
      (node (ref "U1") (pin "34") (pinfunction "NC_34") (pintype "passive"))
    )
    (net (code "68") (name "unconnected-(U1-NC-Pad36)") (class "Default")
      (node (ref "U1") (pin "36") (pinfunction "NC_36") (pintype "passive"))
    )
    (net (code "69") (name "unconnected-(U1-NC-Pad39)") (class "Default")
      (node (ref "U1") (pin "39") (pinfunction "NC_39") (pintype "passive"))
    )
    (net (code "70") (name "unconnected-(U1-TEST-Pad2)") (class "Default")
      (node (ref "U1") (pin "2") (pinfunction "TEST_2") (pintype "passive"))
    )
    (net (code "71") (name "unconnected-(U2-NC-Pad11)") (class "Default")
      (node (ref "U2") (pin "11") (pinfunction "NC_11") (pintype "passive"))
    )
    (net (code "72") (name "unconnected-(U2-NC-Pad12)") (class "Default")
      (node (ref "U2") (pin "12") (pinfunction "NC_12") (pintype "passive"))
    )
    (net (code "73") (name "unconnected-(U2-NC-Pad13)") (class "Default")
      (node (ref "U2") (pin "13") (pinfunction "NC_13") (pintype "passive"))
    )
    (net (code "74") (name "unconnected-(U2-NC-Pad14)") (class "Default")
      (node (ref "U2") (pin "14") (pinfunction "NC_14") (pintype "passive"))
    )
    (net (code "75") (name "unconnected-(U2-NC-Pad15)") (class "Default")
      (node (ref "U2") (pin "15") (pinfunction "NC_15") (pintype "passive"))
    )
    (net (code "76") (name "unconnected-(U2-NC-Pad19)") (class "Default")
      (node (ref "U2") (pin "19") (pinfunction "NC_19") (pintype "passive"))
    )
    (net (code "77") (name "unconnected-(U2-NC-Pad21)") (class "Default")
      (node (ref "U2") (pin "21") (pinfunction "NC_21") (pintype "passive"))
    )
    (net (code "78") (name "unconnected-(U2-NC-Pad27)") (class "Default")
      (node (ref "U2") (pin "27") (pinfunction "NC_27") (pintype "passive"))
    )
    (net (code "79") (name "unconnected-(U2-NC-Pad29)") (class "Default")
      (node (ref "U2") (pin "29") (pinfunction "NC_29") (pintype "passive"))
    )
    (net (code "80") (name "unconnected-(U2-NC-Pad32)") (class "Default")
      (node (ref "U2") (pin "32") (pinfunction "NC_32") (pintype "passive"))
    )
    (net (code "81") (name "unconnected-(U2-NC-Pad33)") (class "Default")
      (node (ref "U2") (pin "33") (pinfunction "NC_33") (pintype "passive"))
    )
    (net (code "82") (name "unconnected-(U2-NC-Pad34)") (class "Default")
      (node (ref "U2") (pin "34") (pinfunction "NC_34") (pintype "passive"))
    )
    (net (code "83") (name "unconnected-(U2-NC-Pad36)") (class "Default")
      (node (ref "U2") (pin "36") (pinfunction "NC_36") (pintype "passive"))
    )
    (net (code "84") (name "unconnected-(U2-NC-Pad39)") (class "Default")
      (node (ref "U2") (pin "39") (pinfunction "NC_39") (pintype "passive"))
    )
    (net (code "85") (name "unconnected-(U2-TEST-Pad2)") (class "Default")
      (node (ref "U2") (pin "2") (pinfunction "TEST_2") (pintype "passive"))
    )
  )
)
